# Support.net
KiCad netlist of a schematic drawn in Altium Designer
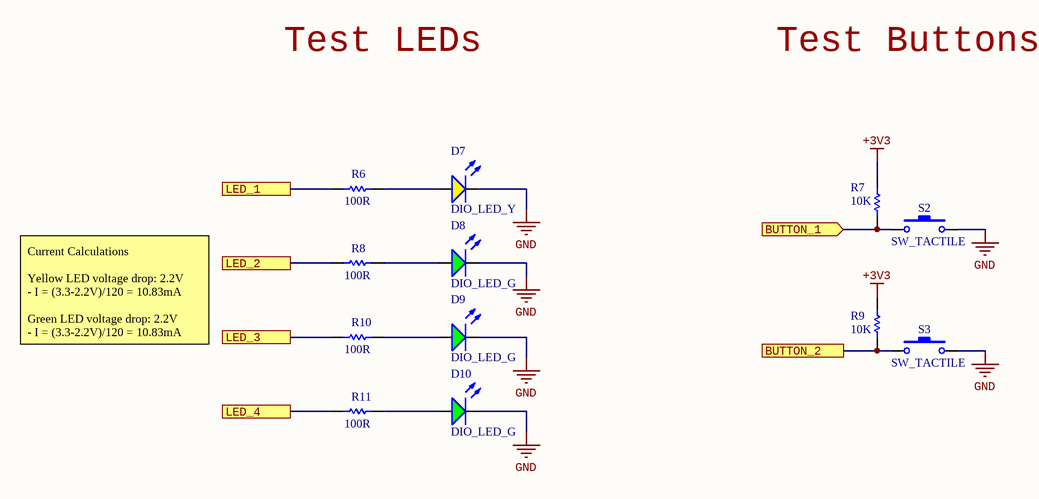
[diagram p0: Support.SchDoc]

(export (version "E")
  (design (tool "Eeschema 10.0.6"))
  (components
    (comp (ref "D7")
      (value "DIO_LED_Y")
      (footprint "LED_0805_LINE")
      (description "LED YELLOW DIFFUSED 0805 SMD")
      (fields (field (name "MANUFACTURER") "OSRAM") (field (name "MPN") "LY R976-PS-36"))
      (libsource (lib "UWRT_Schematic_Library_2020") (part "DIO_LED_Y"))
    )
    (comp (ref "D8")
      (value "DIO_LED_G")
      (footprint "LED_0805_LINE")
      (description "LED GREEN DIFFUSED 0805 SMD")
      (fields (field (name "MANUFACTURER") "OSRAM") (field (name "MPN") "LG R971-KN-1"))
      (libsource (lib "UWRT_Schematic_Library_2020") (part "DIO_LED_G"))
    )
    (comp (ref "D9")
      (value "DIO_LED_G")
      (footprint "LED_0805_LINE")
      (description "LED GREEN DIFFUSED 0805 SMD")
      (fields (field (name "MANUFACTURER") "OSRAM") (field (name "MPN") "LG R971-KN-1"))
      (libsource (lib "UWRT_Schematic_Library_2020") (part "DIO_LED_G"))
    )
    (comp (ref "D10")
      (value "DIO_LED_G")
      (footprint "LED_0805_LINE")
      (description "LED GREEN DIFFUSED 0805 SMD")
      (fields (field (name "MANUFACTURER") "OSRAM") (field (name "MPN") "LG R971-KN-1"))
      (libsource (lib "UWRT_Schematic_Library_2020") (part "DIO_LED_G"))
    )
    (comp (ref "R6")
      (value "100R")
      (footprint "RESC0603(1608)_N")
      (description "RES SMD 100 OHM 1% 1/10W 0603")
      (fields (field (name "MANUFACTURER") "Yageo") (field (name "TOLERANCE") "1%"))
      (libsource (lib "UWRT_Schematic_Library_2020") (part "RES_100R_0603"))
    )
    (comp (ref "R7")
      (value "10K")
      (footprint "RESC0603(1608)_N")
      (description "RES SMD 10K OHM 5% 1/10W 0603")
      (fields (field (name "MANUFACTURER") "Yageo") (field (name "TOLERANCE") "5%"))
      (libsource (lib "UWRT_Schematic_Library_2020") (part "RES_10K_0603"))
    )
    (comp (ref "R8")
      (value "100R")
      (footprint "RESC0603(1608)_N")
      (description "RES SMD 100 OHM 1% 1/10W 0603")
      (fields (field (name "MANUFACTURER") "Yageo") (field (name "TOLERANCE") "1%"))
      (libsource (lib "UWRT_Schematic_Library_2020") (part "RES_100R_0603"))
    )
    (comp (ref "R9")
      (value "10K")
      (footprint "RESC0603(1608)_N")
      (description "RES SMD 10K OHM 5% 1/10W 0603")
      (fields (field (name "MANUFACTURER") "Yageo") (field (name "TOLERANCE") "5%"))
      (libsource (lib "UWRT_Schematic_Library_2020") (part "RES_10K_0603"))
    )
    (comp (ref "R10")
      (value "100R")
      (footprint "RESC0603(1608)_N")
      (description "RES SMD 100 OHM 1% 1/10W 0603")
      (fields (field (name "MANUFACTURER") "Yageo") (field (name "TOLERANCE") "1%"))
      (libsource (lib "UWRT_Schematic_Library_2020") (part "RES_100R_0603"))
    )
    (comp (ref "R11")
      (value "100R")
      (footprint "RESC0603(1608)_N")
      (description "RES SMD 100 OHM 1% 1/10W 0603")
      (fields (field (name "MANUFACTURER") "Yageo") (field (name "TOLERANCE") "1%"))
      (libsource (lib "UWRT_Schematic_Library_2020") (part "RES_100R_0603"))
    )
    (comp (ref "S2")
      (value "SW_TACTILE")
      (footprint "B3U-1100P")
      (description "Tactile Switch (Grey)")
      (fields (field (name "MPN") "B3U-1100P") (field (name "MANUFACTURER") "Omron Electronics Inc-EMC Div"))
      (libsource (lib "UWRT_Schematic_Library_2020") (part "SW_TACTILE"))
    )
    (comp (ref "S3")
      (value "SW_TACTILE")
      (footprint "B3U-1100P")
      (description "Tactile Switch (Grey)")
      (fields (field (name "MPN") "B3U-1100P") (field (name "MANUFACTURER") "Omron Electronics Inc-EMC Div"))
      (libsource (lib "UWRT_Schematic_Library_2020") (part "SW_TACTILE"))
    )
  )
  (nets
    (net (code "1") (name "+3V3") (class "Default")
      (node (ref "R7") (pin "1") (pinfunction "1_1") (pintype "passive"))
      (node (ref "R9") (pin "2") (pinfunction "2_2") (pintype "passive"))
    )
    (net (code "2") (name "/BUTTON_1") (class "Default")
      (node (ref "R7") (pin "2") (pinfunction "2_2") (pintype "passive"))
      (node (ref "S2") (pin "1") (pinfunction "1_1") (pintype "passive"))
    )
    (net (code "3") (name "/BUTTON_2") (class "Default")
      (node (ref "R9") (pin "1") (pinfunction "1_1") (pintype "passive"))
      (node (ref "S3") (pin "1") (pinfunction "1_1") (pintype "passive"))
    )
    (net (code "4") (name "/LED_1") (class "Default")
      (node (ref "R6") (pin "1") (pinfunction "1_1") (pintype "passive"))
    )
    (net (code "5") (name "/LED_2") (class "Default")
      (node (ref "R8") (pin "1") (pinfunction "1_1") (pintype "passive"))
    )
    (net (code "6") (name "/LED_3") (class "Default")
      (node (ref "R10") (pin "1") (pinfunction "1_1") (pintype "passive"))
    )
    (net (code "7") (name "/LED_4") (class "Default")
      (node (ref "R11") (pin "1") (pinfunction "1_1") (pintype "passive"))
    )
    (net (code "8") (name "GND") (class "Default")
      (node (ref "D10") (pin "2") (pinfunction "K_2") (pintype "passive"))
      (node (ref "D7") (pin "2") (pinfunction "K_2") (pintype "passive"))
      (node (ref "D8") (pin "2") (pinfunction "K_2") (pintype "passive"))
      (node (ref "D9") (pin "2") (pinfunction "K_2") (pintype "passive"))
      (node (ref "S2") (pin "2") (pinfunction "2_2") (pintype "passive"))
      (node (ref "S3") (pin "2") (pinfunction "2_2") (pintype "passive"))
    )
    (net (code "9") (name "Net-(D7-A)") (class "Default")
      (node (ref "D7") (pin "1") (pinfunction "A_1") (pintype "passive"))
      (node (ref "R6") (pin "2") (pinfunction "2_2") (pintype "passive"))
    )
    (net (code "10") (name "Net-(D8-A)") (class "Default")
      (node (ref "D8") (pin "1") (pinfunction "A_1") (pintype "passive"))
      (node (ref "R8") (pin "2") (pinfunction "2_2") (pintype "passive"))
    )
    (net (code "11") (name "Net-(D9-A)") (class "Default")
      (node (ref "D9") (pin "1") (pinfunction "A_1") (pintype "passive"))
      (node (ref "R10") (pin "2") (pinfunction "2_2") (pintype "passive"))
    )
    (net (code "12") (name "Net-(D10-A)") (class "Default")
      (node (ref "D10") (pin "1") (pinfunction "A_1") (pintype "passive"))
      (node (ref "R11") (pin "2") (pinfunction "2_2") (pintype "passive"))
    )
  )
)
